# MAX7219_8X8LED_BOARD.net
KiCad netlist of a schematic drawn in Altium Designer
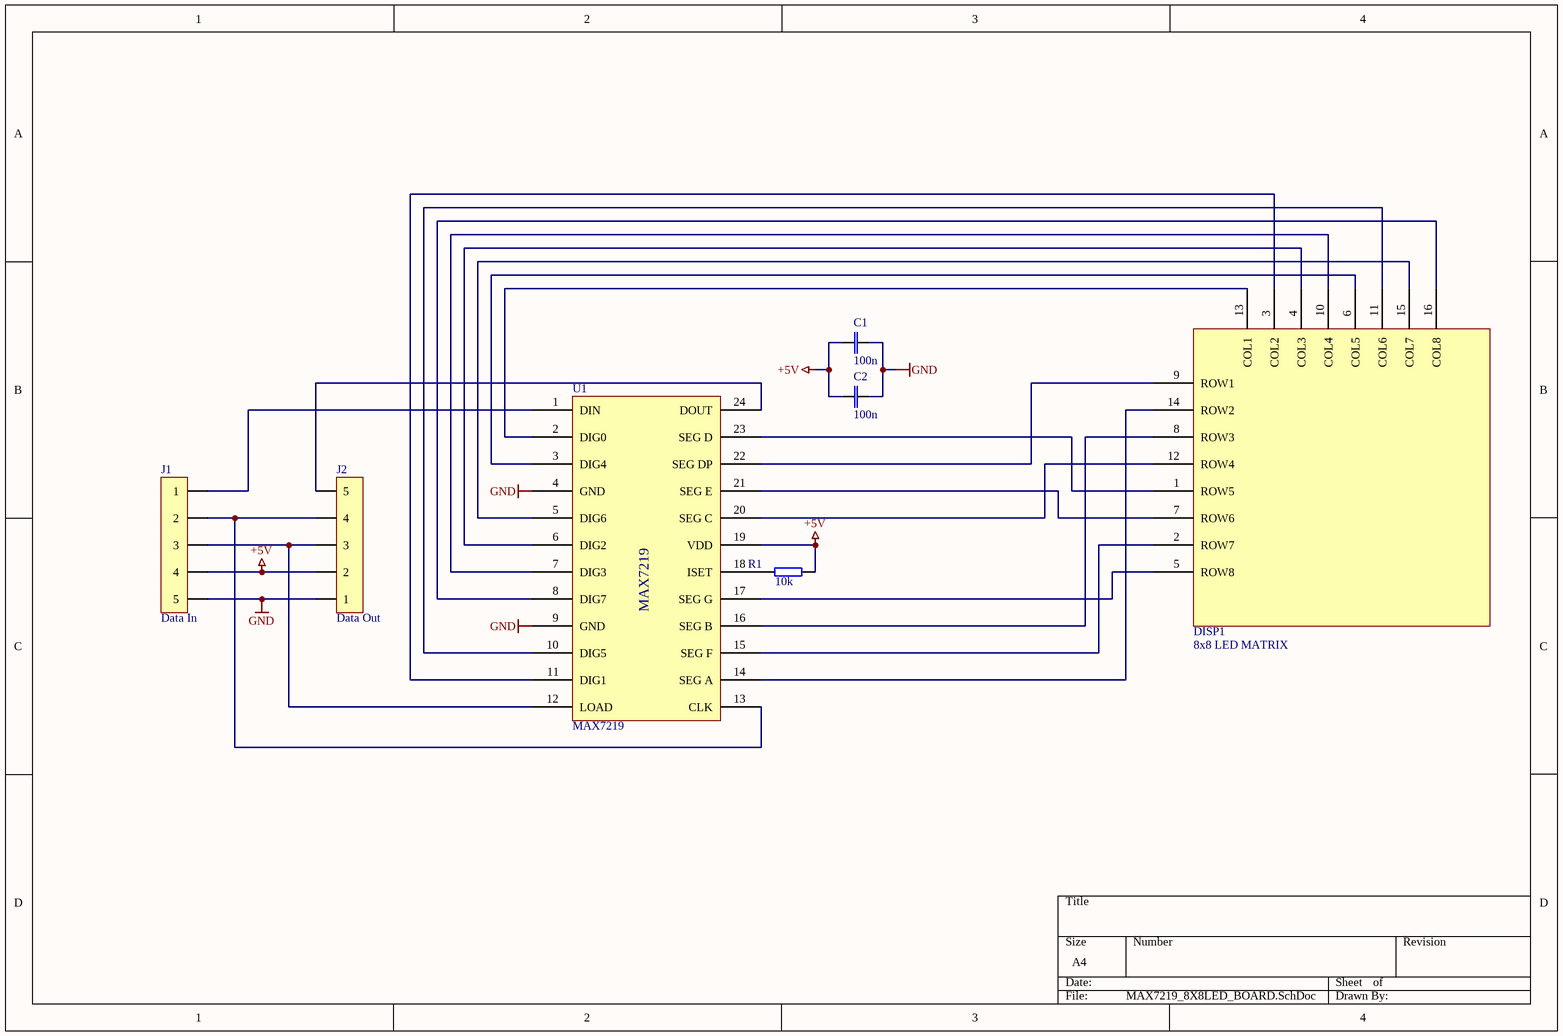
[diagram p0: MAX7219_8X8LED_BOARD.SchDoc]

(export (version "E")
  (design (tool "Eeschema 10.0.6"))
  (components
    (comp (ref "C1")
      (value "100n")
      (footprint "CAP 0805")
      (description "NON POLARIZED CAPACITOR")
      (libsource (lib "sajatSCH") (part "CAP"))
    )
    (comp (ref "C2")
      (value "100n")
      (footprint "CAP 0805")
      (description "NON POLARIZED CAPACITOR")
      (libsource (lib "sajatSCH") (part "CAP"))
    )
    (comp (ref "DISP1")
      (value "8x8 LED MATRIX")
      (footprint "8x8*60mm LED MATRIX")
      (description "60x60mm 8x8 LED Matrix display")
      (libsource (lib "sajatSCH") (part "8x8 60mm LED MATRIX"))
    )
    (comp (ref "J1")
      (value "Data In")
      (footprint "SIL5_90")
      (description "5 PIN HEADER")
      (libsource (lib "sajatSCH") (part "HEADER5"))
    )
    (comp (ref "J2")
      (value "Data Out")
      (footprint "SIL5_90")
      (description "5 PIN HEADER")
      (libsource (lib "") (part "HEADER5_1"))
    )
    (comp (ref "R1")
      (value "10k")
      (footprint "RES 0805")
      (description "RESISTOR")
      (libsource (lib "sajatSCH") (part "RES"))
    )
    (comp (ref "U1")
      (value "MAX7219")
      (footprint "SO24")
      (description "8X8 LED DRIVER IC")
      (libsource (lib "sajatSCH") (part "MAX7219"))
    )
  )
  (nets
    (net (code "1") (name "+5V") (class "Default")
      (node (ref "C1") (pin "1") (pinfunction "1_1") (pintype "passive"))
      (node (ref "C2") (pin "1") (pinfunction "1_1") (pintype "passive"))
      (node (ref "J1") (pin "4") (pinfunction "4_4") (pintype "passive"))
      (node (ref "J2") (pin "2") (pinfunction "2_2") (pintype "passive"))
      (node (ref "R1") (pin "2") (pinfunction "2_2") (pintype "passive"))
      (node (ref "U1") (pin "19") (pinfunction "VDD_19") (pintype "passive"))
    )
    (net (code "2") (name "GND") (class "Default")
      (node (ref "C1") (pin "2") (pinfunction "2_2") (pintype "passive"))
      (node (ref "C2") (pin "2") (pinfunction "2_2") (pintype "passive"))
      (node (ref "J1") (pin "5") (pinfunction "5_5") (pintype "passive"))
      (node (ref "J2") (pin "1") (pinfunction "1_1") (pintype "passive"))
      (node (ref "U1") (pin "4") (pinfunction "GND_4") (pintype "passive"))
      (node (ref "U1") (pin "9") (pinfunction "GND_9") (pintype "passive"))
    )
    (net (code "3") (name "Net-(DISP1-COL1)") (class "Default")
      (node (ref "DISP1") (pin "13") (pinfunction "COL1_13") (pintype "passive"))
      (node (ref "U1") (pin "2") (pinfunction "DIG0_2") (pintype "passive"))
    )
    (net (code "4") (name "Net-(DISP1-COL2)") (class "Default")
      (node (ref "DISP1") (pin "3") (pinfunction "COL2_3") (pintype "passive"))
      (node (ref "U1") (pin "11") (pinfunction "DIG1_11") (pintype "passive"))
    )
    (net (code "5") (name "Net-(DISP1-COL3)") (class "Default")
      (node (ref "DISP1") (pin "4") (pinfunction "COL3_4") (pintype "passive"))
      (node (ref "U1") (pin "6") (pinfunction "DIG2_6") (pintype "passive"))
    )
    (net (code "6") (name "Net-(DISP1-COL4)") (class "Default")
      (node (ref "DISP1") (pin "10") (pinfunction "COL4_10") (pintype "passive"))
      (node (ref "U1") (pin "7") (pinfunction "DIG3_7") (pintype "passive"))
    )
    (net (code "7") (name "Net-(DISP1-COL5)") (class "Default")
      (node (ref "DISP1") (pin "6") (pinfunction "COL5_6") (pintype "passive"))
      (node (ref "U1") (pin "3") (pinfunction "DIG4_3") (pintype "passive"))
    )
    (net (code "8") (name "Net-(DISP1-COL6)") (class "Default")
      (node (ref "DISP1") (pin "11") (pinfunction "COL6_11") (pintype "passive"))
      (node (ref "U1") (pin "10") (pinfunction "DIG5_10") (pintype "passive"))
    )
    (net (code "9") (name "Net-(DISP1-COL7)") (class "Default")
      (node (ref "DISP1") (pin "15") (pinfunction "COL7_15") (pintype "passive"))
      (node (ref "U1") (pin "5") (pinfunction "DIG6_5") (pintype "passive"))
    )
    (net (code "10") (name "Net-(DISP1-COL8)") (class "Default")
      (node (ref "DISP1") (pin "16") (pinfunction "COL8_16") (pintype "passive"))
      (node (ref "U1") (pin "8") (pinfunction "DIG7_8") (pintype "passive"))
    )
    (net (code "11") (name "Net-(DISP1-ROW1)") (class "Default")
      (node (ref "DISP1") (pin "9") (pinfunction "ROW1_9") (pintype "passive"))
      (node (ref "U1") (pin "22") (pinfunction "SEG_DP_22") (pintype "passive"))
    )
    (net (code "12") (name "Net-(DISP1-ROW2)") (class "Default")
      (node (ref "DISP1") (pin "14") (pinfunction "ROW2_14") (pintype "passive"))
      (node (ref "U1") (pin "14") (pinfunction "SEG_A_14") (pintype "passive"))
    )
    (net (code "13") (name "Net-(DISP1-ROW3)") (class "Default")
      (node (ref "DISP1") (pin "8") (pinfunction "ROW3_8") (pintype "passive"))
      (node (ref "U1") (pin "16") (pinfunction "SEG_B_16") (pintype "passive"))
    )
    (net (code "14") (name "Net-(DISP1-ROW4)") (class "Default")
      (node (ref "DISP1") (pin "12") (pinfunction "ROW4_12") (pintype "passive"))
      (node (ref "U1") (pin "20") (pinfunction "SEG_C_20") (pintype "passive"))
    )
    (net (code "15") (name "Net-(DISP1-ROW5)") (class "Default")
      (node (ref "DISP1") (pin "1") (pinfunction "ROW5_1") (pintype "passive"))
      (node (ref "U1") (pin "23") (pinfunction "SEG_D_23") (pintype "passive"))
    )
    (net (code "16") (name "Net-(DISP1-ROW6)") (class "Default")
      (node (ref "DISP1") (pin "7") (pinfunction "ROW6_7") (pintype "passive"))
      (node (ref "U1") (pin "21") (pinfunction "SEG_E_21") (pintype "passive"))
    )
    (net (code "17") (name "Net-(DISP1-ROW7)") (class "Default")
      (node (ref "DISP1") (pin "2") (pinfunction "ROW7_2") (pintype "passive"))
      (node (ref "U1") (pin "15") (pinfunction "SEG_F_15") (pintype "passive"))
    )
    (net (code "18") (name "Net-(DISP1-ROW8)") (class "Default")
      (node (ref "DISP1") (pin "5") (pinfunction "ROW8_5") (pintype "passive"))
      (node (ref "U1") (pin "17") (pinfunction "SEG_G_17") (pintype "passive"))
    )
    (net (code "19") (name "Net-(U1-CLK)") (class "Default")
      (node (ref "J1") (pin "2") (pinfunction "2_2") (pintype "passive"))
      (node (ref "J2") (pin "4") (pinfunction "4_4") (pintype "passive"))
      (node (ref "U1") (pin "13") (pinfunction "CLK_13") (pintype "passive"))
    )
    (net (code "20") (name "Net-(U1-DIN)") (class "Default")
      (node (ref "J1") (pin "1") (pinfunction "1_1") (pintype "passive"))
      (node (ref "U1") (pin "1") (pinfunction "DIN_1") (pintype "passive"))
    )
    (net (code "21") (name "Net-(U1-DOUT)") (class "Default")
      (node (ref "J2") (pin "5") (pinfunction "5_5") (pintype "passive"))
      (node (ref "U1") (pin "24") (pinfunction "DOUT_24") (pintype "passive"))
    )
    (net (code "22") (name "Net-(U1-ISET)") (class "Default")
      (node (ref "R1") (pin "1") (pinfunction "1_1") (pintype "passive"))
      (node (ref "U1") (pin "18") (pinfunction "ISET_18") (pintype "passive"))
    )
    (net (code "23") (name "Net-(U1-LOAD)") (class "Default")
      (node (ref "J1") (pin "3") (pinfunction "3_3") (pintype "passive"))
      (node (ref "J2") (pin "3") (pinfunction "3_3") (pintype "passive"))
      (node (ref "U1") (pin "12") (pinfunction "LOAD_12") (pintype "passive"))
    )
  )
)
